# VCONV-DAC.net
KiCad netlist of a schematic drawn in Altium Designer
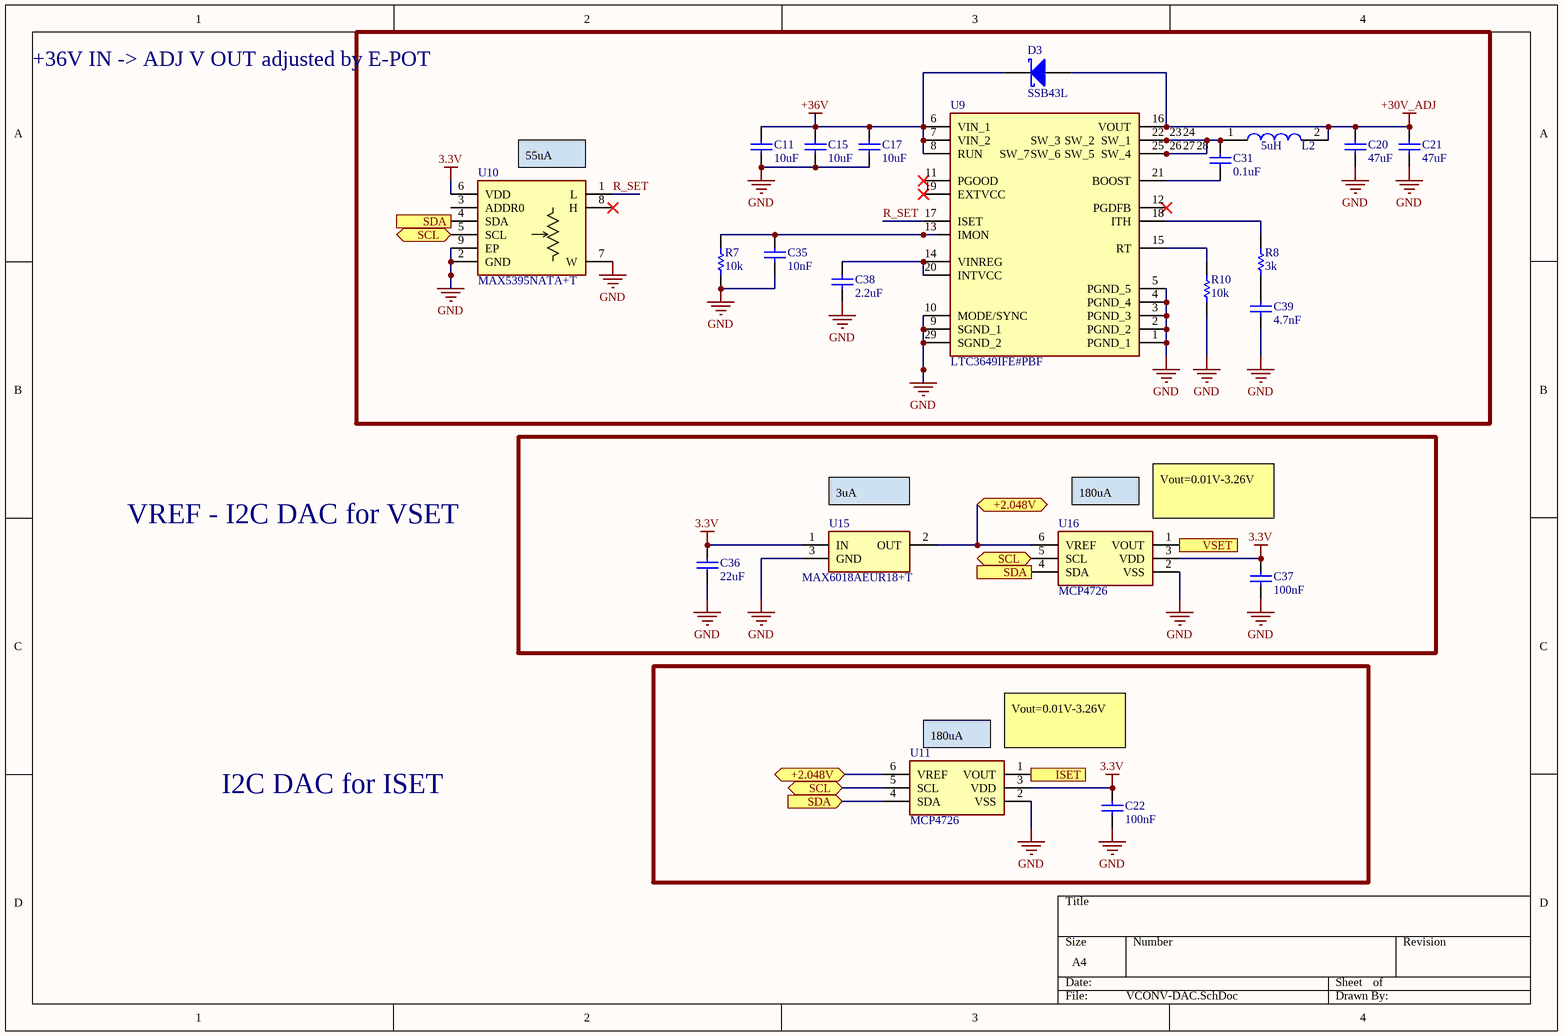
[diagram p0: VCONV-DAC.SchDoc]

(export (version "E")
  (design (tool "Eeschema 10.0.6"))
  (components
    (comp (ref "C11")
      (value "10uF")
      (footprint "Cap_0603")
      (description "Capacitor")
      (fields (field (name "Comment") "Cap") (field (name "PUBLISHER") "Altium Limited"))
      (libsource (lib "cc cv power supply") (part "Cap"))
    )
    (comp (ref "C15")
      (value "10uF")
      (footprint "Cap_0603")
      (description "Capacitor")
      (fields (field (name "Comment") "Cap") (field (name "PUBLISHER") "Altium Limited"))
      (libsource (lib "cc cv power supply") (part "Cap"))
    )
    (comp (ref "C17")
      (value "10uF")
      (footprint "Cap_0603")
      (description "Capacitor")
      (fields (field (name "Comment") "Cap") (field (name "PUBLISHER") "Altium Limited"))
      (libsource (lib "cc cv power supply") (part "Cap"))
    )
    (comp (ref "C20")
      (value "47uF")
      (footprint "Cap_0603")
      (description "Capacitor")
      (fields (field (name "Comment") "Cap") (field (name "PUBLISHER") "Altium Limited"))
      (libsource (lib "cc cv power supply") (part "Cap"))
    )
    (comp (ref "C21")
      (value "47uF")
      (footprint "Cap_0603")
      (description "Capacitor")
      (fields (field (name "Comment") "Cap") (field (name "PUBLISHER") "Altium Limited"))
      (libsource (lib "cc cv power supply") (part "Cap"))
    )
    (comp (ref "C22")
      (value "100nF")
      (footprint "Cap_0603")
      (description "Capacitor")
      (fields (field (name "Comment") "Cap") (field (name "PUBLISHER") "Altium Limited"))
      (libsource (lib "cc cv power supply") (part "Cap"))
    )
    (comp (ref "C31")
      (value "0.1uF")
      (footprint "Cap_0603")
      (description "Capacitor")
      (fields (field (name "Comment") "Cap") (field (name "PUBLISHER") "Altium Limited"))
      (libsource (lib "cc cv power supply") (part "Cap"))
    )
    (comp (ref "C35")
      (value "10nF")
      (footprint "Cap_0603")
      (description "Capacitor")
      (fields (field (name "Comment") "Cap") (field (name "PUBLISHER") "Altium Limited"))
      (libsource (lib "cc cv power supply") (part "Cap"))
    )
    (comp (ref "C36")
      (value "22uF")
      (footprint "Cap_0603")
      (description "Capacitor")
      (fields (field (name "Comment") "Cap") (field (name "PUBLISHER") "Altium Limited"))
      (libsource (lib "cc cv power supply") (part "Cap"))
    )
    (comp (ref "C37")
      (value "100nF")
      (footprint "Cap_0603")
      (description "Capacitor")
      (fields (field (name "Comment") "Cap") (field (name "PUBLISHER") "Altium Limited"))
      (libsource (lib "cc cv power supply") (part "Cap"))
    )
    (comp (ref "C38")
      (value "2.2uF")
      (footprint "Cap_0603")
      (description "Capacitor")
      (fields (field (name "Comment") "Cap") (field (name "PUBLISHER") "Altium Limited"))
      (libsource (lib "cc cv power supply") (part "Cap"))
    )
    (comp (ref "C39")
      (value "4.7nF")
      (footprint "Cap_0603")
      (description "Capacitor")
      (fields (field (name "Comment") "Cap") (field (name "PUBLISHER") "Altium Limited"))
      (libsource (lib "cc cv power supply") (part "Cap"))
    )
    (comp (ref "D3")
      (value "SSB43L")
      (footprint "DO-214AA(SMB)")
      (description "Schottky Rectifier, 40 V, 4 A, Single, DO-214AA (SMB), 2 Pins, 490 mV")
      (libsource (lib "DCSupplyHubLib") (part "SSB43L"))
    )
    (comp (ref "L2")
      (value "5uH")
      (footprint "IND_TCK-141_TRP")
      (description "FIXED IND 5.6UH 3.5A 90MOHM SMD")
      (fields
        (field (name "MANUFACTURER_PART_NUMBER") "TCK-141")
        (field (name "COPYRIGHT") "Copyright (C) 2023 Ultra Librarian. All rights reserved.")
      )
      (libsource (lib "DCSupplyHubLib") (part "TCK-141"))
    )
    (comp (ref "R7")
      (value "10k")
      (footprint "RES_0805")
      (description "Resistor")
      (fields (field (name "Comment") "Res1") (field (name "PUBLISHER") "Altium Limited"))
      (libsource (lib "cc cv power supply") (part "Res1"))
    )
    (comp (ref "R8")
      (value "3k")
      (footprint "RES_0805")
      (description "Resistor")
      (fields (field (name "Comment") "Res1") (field (name "PUBLISHER") "Altium Limited"))
      (libsource (lib "cc cv power supply") (part "Res1"))
    )
    (comp (ref "R10")
      (value "10k")
      (footprint "RES_0805")
      (description "Resistor")
      (fields (field (name "Comment") "Res1") (field (name "PUBLISHER") "Altium Limited"))
      (libsource (lib "cc cv power supply") (part "Res1"))
    )
    (comp (ref "U9")
      (value "LTC3649IFE#PBF")
      (footprint "SOP65P640X120-29N")
      (description "60V, 4A Synchronous Step-Down Regulator with Rail-to-Rail Programmable Output")
      (fields (field (name "MOUSER PART NUMBER") "584-LTC3649IFE#PBF"))
      (libsource (lib "DCSupplyHubLib") (part "LTC3649IFE#PBF"))
    )
    (comp (ref "U10")
      (value "MAX5395NATA+T")
      (footprint "SamacSys:SON50P200X200X80-9N-D")
      (description "ingle, 256-Tap Volatile, I2C, Low-Voltage Linear\r\nTaper Digital Potentiometer")
      (fields (field (name "MOUSER PART NUMBER") "700-MAX5395NATA+T"))
      (libsource (lib "SamacSys") (part "MAX5395NATA+T"))
    )
    (comp (ref "U11")
      (value "MCP4726")
      (footprint "SamacSys:SOT95P270X145-6N")
      (description "12-Bit Digital-to-Analog Converter with EEPROM Memory")
      (fields
        (field (name "MANUFACTURER_PART_NUMBER") "MCP4725A0T-E/CH")
        (field (name "MOUSER PART NUMBER") "579-MCP4725A0TECH")
      )
      (libsource (lib "SamacSys") (part "MCP4725A0T-E_CH"))
    )
    (comp (ref "U15")
      (value "MAX6018AEUR18+T")
      (footprint "SamacSys:SOT95P237X112-3N")
      (description "Precision, Micropower, 1.8V Supply,\r\nLow-Dropout, SOT23 Voltage Reference")
      (fields (field (name "MOUSER PART NUMBER") "700-MAX6018AEUR18T"))
      (libsource (lib "SamacSys") (part "MAX6018AEUR18+T"))
    )
    (comp (ref "U16")
      (value "MCP4726")
      (footprint "SamacSys:SOT95P270X145-6N")
      (description "12-Bit Digital-to-Analog Converter with EEPROM Memory")
      (fields
        (field (name "MANUFACTURER_PART_NUMBER") "MCP4725A0T-E/CH")
        (field (name "MOUSER PART NUMBER") "579-MCP4725A0TECH")
      )
      (libsource (lib "SamacSys") (part "MCP4725A0T-E_CH"))
    )
  )
  (nets
    (net (code "1") (name "+30V_ADJ") (class "Default")
      (node (ref "C20") (pin "1") (pinfunction "1_1") (pintype "passive"))
      (node (ref "C21") (pin "1") (pinfunction "1_1") (pintype "passive"))
      (node (ref "D3") (pin "A") (pinfunction "A_A") (pintype "passive"))
      (node (ref "L2") (pin "2") (pinfunction "2_2") (pintype "passive"))
      (node (ref "U9") (pin "16") (pinfunction "VOUT_16") (pintype "passive"))
    )
    (net (code "2") (name "+36V") (class "Default")
      (node (ref "C11") (pin "1") (pinfunction "1_1") (pintype "passive"))
      (node (ref "C15") (pin "1") (pinfunction "1_1") (pintype "passive"))
      (node (ref "C17") (pin "1") (pinfunction "1_1") (pintype "passive"))
      (node (ref "D3") (pin "K") (pinfunction "K_K") (pintype "passive"))
      (node (ref "U9") (pin "6") (pinfunction "VIN_1_6") (pintype "passive"))
      (node (ref "U9") (pin "7") (pinfunction "VIN_2_7") (pintype "passive"))
      (node (ref "U9") (pin "8") (pinfunction "RUN_8") (pintype "passive"))
    )
    (net (code "3") (name "/+2.048V") (class "Default")
      (node (ref "U11") (pin "6") (pinfunction "VREF_6") (pintype "passive"))
      (node (ref "U15") (pin "2") (pinfunction "OUT_2") (pintype "passive"))
      (node (ref "U16") (pin "6") (pinfunction "VREF_6") (pintype "passive"))
    )
    (net (code "4") (name "/ISET") (class "Default")
      (node (ref "U11") (pin "1") (pinfunction "VOUT_1") (pintype "passive"))
    )
    (net (code "5") (name "/R_SET") (class "Default")
      (node (ref "U10") (pin "1") (pinfunction "L_1") (pintype "passive"))
      (node (ref "U9") (pin "17") (pinfunction "ISET_17") (pintype "passive"))
    )
    (net (code "6") (name "/SCL") (class "Default")
      (node (ref "U10") (pin "5") (pinfunction "SCL_5") (pintype "passive"))
      (node (ref "U11") (pin "5") (pinfunction "SCL_5") (pintype "passive"))
      (node (ref "U16") (pin "5") (pinfunction "SCL_5") (pintype "passive"))
    )
    (net (code "7") (name "/SDA") (class "Default")
      (node (ref "U10") (pin "4") (pinfunction "SDA_4") (pintype "passive"))
      (node (ref "U11") (pin "4") (pinfunction "SDA_4") (pintype "passive"))
      (node (ref "U16") (pin "4") (pinfunction "SDA_4") (pintype "passive"))
    )
    (net (code "8") (name "/VSET") (class "Default")
      (node (ref "U16") (pin "1") (pinfunction "VOUT_1") (pintype "passive"))
    )
    (net (code "9") (name "3.3V") (class "Default")
      (node (ref "C22") (pin "1") (pinfunction "1_1") (pintype "passive"))
      (node (ref "C36") (pin "1") (pinfunction "1_1") (pintype "passive"))
      (node (ref "C37") (pin "1") (pinfunction "1_1") (pintype "passive"))
      (node (ref "U10") (pin "6") (pinfunction "VDD_6") (pintype "passive"))
      (node (ref "U11") (pin "3") (pinfunction "VDD_3") (pintype "passive"))
      (node (ref "U15") (pin "1") (pinfunction "IN_1") (pintype "passive"))
      (node (ref "U16") (pin "3") (pinfunction "VDD_3") (pintype "passive"))
    )
    (net (code "10") (name "GND") (class "Default")
      (node (ref "C11") (pin "2") (pinfunction "2_2") (pintype "passive"))
      (node (ref "C15") (pin "2") (pinfunction "2_2") (pintype "passive"))
      (node (ref "C17") (pin "2") (pinfunction "2_2") (pintype "passive"))
      (node (ref "C20") (pin "2") (pinfunction "2_2") (pintype "passive"))
      (node (ref "C21") (pin "2") (pinfunction "2_2") (pintype "passive"))
      (node (ref "C22") (pin "2") (pinfunction "2_2") (pintype "passive"))
      (node (ref "C35") (pin "2") (pinfunction "2_2") (pintype "passive"))
      (node (ref "C36") (pin "2") (pinfunction "2_2") (pintype "passive"))
      (node (ref "C37") (pin "2") (pinfunction "2_2") (pintype "passive"))
      (node (ref "C38") (pin "2") (pinfunction "2_2") (pintype "passive"))
      (node (ref "C39") (pin "2") (pinfunction "2_2") (pintype "passive"))
      (node (ref "R10") (pin "1") (pinfunction "1_1") (pintype "passive"))
      (node (ref "R7") (pin "1") (pinfunction "1_1") (pintype "passive"))
      (node (ref "U10") (pin "2") (pinfunction "GND_2") (pintype "passive"))
      (node (ref "U10") (pin "7") (pinfunction "W_7") (pintype "passive"))
      (node (ref "U10") (pin "9") (pinfunction "EP_9") (pintype "passive"))
      (node (ref "U11") (pin "2") (pinfunction "VSS_2") (pintype "passive"))
      (node (ref "U15") (pin "3") (pinfunction "GND_3") (pintype "passive"))
      (node (ref "U16") (pin "2") (pinfunction "VSS_2") (pintype "passive"))
      (node (ref "U9") (pin "1") (pinfunction "PGND_1_1") (pintype "passive"))
      (node (ref "U9") (pin "10") (pinfunction "MODE/SYNC_10") (pintype "passive"))
      (node (ref "U9") (pin "2") (pinfunction "PGND_2_2") (pintype "passive"))
      (node (ref "U9") (pin "29") (pinfunction "SGND_2_29") (pintype "passive"))
      (node (ref "U9") (pin "3") (pinfunction "PGND_3_3") (pintype "passive"))
      (node (ref "U9") (pin "4") (pinfunction "PGND_4_4") (pintype "passive"))
      (node (ref "U9") (pin "5") (pinfunction "PGND_5_5") (pintype "passive"))
      (node (ref "U9") (pin "9") (pinfunction "SGND_1_9") (pintype "passive"))
    )
    (net (code "11") (name "Net-(C39-Pad1)") (class "Default")
      (node (ref "C39") (pin "1") (pinfunction "1_1") (pintype "passive"))
      (node (ref "R8") (pin "1") (pinfunction "1_1") (pintype "passive"))
    )
    (net (code "12") (name "Net-(U9-BOOST)") (class "Default")
      (node (ref "C31") (pin "2") (pinfunction "2_2") (pintype "passive"))
      (node (ref "U9") (pin "21") (pinfunction "BOOST_21") (pintype "passive"))
    )
    (net (code "13") (name "Net-(U9-IMON)") (class "Default")
      (node (ref "C35") (pin "1") (pinfunction "1_1") (pintype "passive"))
      (node (ref "R7") (pin "2") (pinfunction "2_2") (pintype "passive"))
      (node (ref "U9") (pin "13") (pinfunction "IMON_13") (pintype "passive"))
    )
    (net (code "14") (name "Net-(U9-INTVCC)") (class "Default")
      (node (ref "C38") (pin "1") (pinfunction "1_1") (pintype "passive"))
      (node (ref "U9") (pin "14") (pinfunction "VINREG_14") (pintype "passive"))
      (node (ref "U9") (pin "20") (pinfunction "INTVCC_20") (pintype "passive"))
    )
    (net (code "15") (name "Net-(U9-ITH)") (class "Default")
      (node (ref "R8") (pin "2") (pinfunction "2_2") (pintype "passive"))
      (node (ref "U9") (pin "18") (pinfunction "ITH_18") (pintype "passive"))
    )
    (net (code "16") (name "Net-(U9-RT)") (class "Default")
      (node (ref "R10") (pin "2") (pinfunction "2_2") (pintype "passive"))
      (node (ref "U9") (pin "15") (pinfunction "RT_15") (pintype "passive"))
    )
    (net (code "17") (name "Net-(U9-SW_1)") (class "Default")
      (node (ref "C31") (pin "1") (pinfunction "1_1") (pintype "passive"))
      (node (ref "L2") (pin "1") (pinfunction "1_1") (pintype "passive"))
      (node (ref "U9") (pin "22") (pinfunction "SW_1_22") (pintype "passive"))
      (node (ref "U9") (pin "23") (pinfunction "SW_2_23") (pintype "passive"))
      (node (ref "U9") (pin "24") (pinfunction "SW_3_24") (pintype "passive"))
      (node (ref "U9") (pin "25") (pinfunction "SW_4_25") (pintype "passive"))
      (node (ref "U9") (pin "26") (pinfunction "SW_5_26") (pintype "passive"))
      (node (ref "U9") (pin "27") (pinfunction "SW_6_27") (pintype "passive"))
      (node (ref "U9") (pin "28") (pinfunction "SW_7_28") (pintype "passive"))
    )
    (net (code "18") (name "unconnected-(U9-EXTVCC-Pad19)") (class "Default")
      (node (ref "U9") (pin "19") (pinfunction "EXTVCC_19") (pintype "passive+no_connect"))
    )
    (net (code "19") (name "unconnected-(U9-PGDFB-Pad12)") (class "Default")
      (node (ref "U9") (pin "12") (pinfunction "PGDFB_12") (pintype "passive+no_connect"))
    )
    (net (code "20") (name "unconnected-(U9-PGOOD-Pad11)") (class "Default")
      (node (ref "U9") (pin "11") (pinfunction "PGOOD_11") (pintype "passive+no_connect"))
    )
    (net (code "21") (name "unconnected-(U10-ADDR0-Pad3)") (class "Default")
      (node (ref "U10") (pin "3") (pinfunction "ADDR0_3") (pintype "passive"))
    )
    (net (code "22") (name "unconnected-(U10-H-Pad8)") (class "Default")
      (node (ref "U10") (pin "8") (pinfunction "H_8") (pintype "passive+no_connect"))
    )
  )
)
